# RS232.net
KiCad netlist of a schematic drawn in Altium Designer
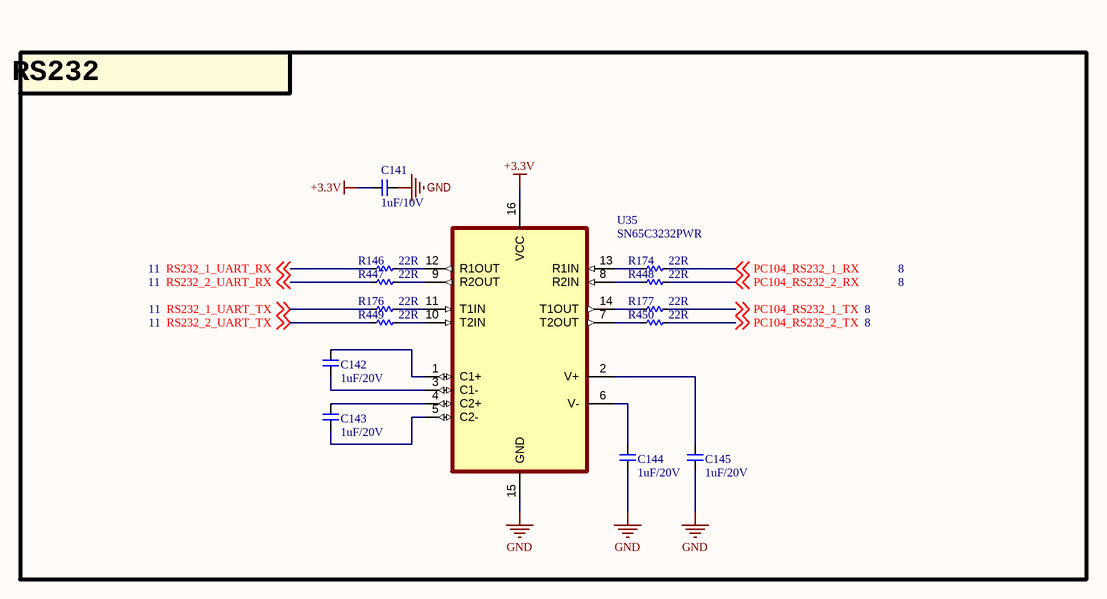
[diagram p0: RS232.SchDoc]

(export (version "E")
  (design (tool "Eeschema 10.0.6"))
  (components
    (comp (ref "C141")
      (value "1uF/10V")
      (footprint "CAP_C_1005X50_L")
      (description "CAP CHIP")
      (libsource (lib "LABLIB") (part "_CAP_C_2"))
    )
    (comp (ref "C142")
      (value "1uF/20V")
      (footprint "CAP_C_1005X50_L")
      (description "CAP CHIP")
      (libsource (lib "LABLIB") (part "_CAP_C_2"))
    )
    (comp (ref "C143")
      (value "1uF/20V")
      (footprint "CAP_C_1005X50_L")
      (description "CAP CHIP")
      (libsource (lib "LABLIB") (part "_CAP_C_2"))
    )
    (comp (ref "C144")
      (value "1uF/20V")
      (footprint "CAP_C_1005X50_L")
      (description "CAP CHIP")
      (libsource (lib "LABLIB") (part "_CAP_C_2"))
    )
    (comp (ref "C145")
      (value "1uF/20V")
      (footprint "CAP_C_1005X50_L")
      (description "CAP CHIP")
      (libsource (lib "LABLIB") (part "_CAP_C_2"))
    )
    (comp (ref "R146")
      (value "22R")
      (footprint "RES_C_1005x30_L")
      (description "RES")
      (libsource (lib "LABLIB") (part "_RES_B_2"))
    )
    (comp (ref "R174")
      (value "22R")
      (footprint "RES_C_1005x30_L")
      (description "RES")
      (libsource (lib "LABLIB") (part "_RES_B_2"))
    )
    (comp (ref "R176")
      (value "22R")
      (footprint "RES_C_1005x30_L")
      (description "RES")
      (libsource (lib "LABLIB") (part "_RES_B_2"))
    )
    (comp (ref "R177")
      (value "22R")
      (footprint "RES_C_1005x30_L")
      (description "RES")
      (libsource (lib "LABLIB") (part "_RES_B_2"))
    )
    (comp (ref "R447")
      (value "22R")
      (footprint "RES_C_1005x30_L")
      (description "RES")
      (libsource (lib "LABLIB") (part "_RES_B_2"))
    )
    (comp (ref "R448")
      (value "22R")
      (footprint "RES_C_1005x30_L")
      (description "RES")
      (libsource (lib "LABLIB") (part "_RES_B_2"))
    )
    (comp (ref "R449")
      (value "22R")
      (footprint "RES_C_1005x30_L")
      (description "RES")
      (libsource (lib "LABLIB") (part "_RES_B_2"))
    )
    (comp (ref "R450")
      (value "22R")
      (footprint "RES_C_1005x30_L")
      (description "RES")
      (libsource (lib "LABLIB") (part "_RES_B_2"))
    )
    (comp (ref "U35")
      (value "SN65C3232PWR")
      (footprint "SOP65P640X120-16N")
      (description "2/2 Transceiver Full RS232 16-TSSOP 1GHz")
      (fields (field (name "MF") "Analog Devices") (field (name "MP") "MAX3232CSE+T"))
      (libsource (lib "LABLIB") (part "IC_RS232_SN65C3232PWR"))
    )
  )
  (nets
    (net (code "1") (name "+3.3V") (class "Default")
      (node (ref "C141") (pin "2") (pinfunction "2_2") (pintype "passive"))
      (node (ref "U35") (pin "16") (pinfunction "VCC_16") (pintype "power_in"))
    )
    (net (code "2") (name "GND") (class "Default")
      (node (ref "C141") (pin "1") (pinfunction "1_1") (pintype "passive"))
      (node (ref "C144") (pin "1") (pinfunction "1_1") (pintype "passive"))
      (node (ref "C145") (pin "1") (pinfunction "1_1") (pintype "passive"))
      (node (ref "U35") (pin "15") (pinfunction "GND_15") (pintype "power_in"))
    )
    (net (code "3") (name "Net-(U35-C1+)") (class "Default")
      (node (ref "C142") (pin "1") (pinfunction "1_1") (pintype "passive"))
      (node (ref "U35") (pin "1") (pinfunction "C1+_1") (pintype "bidirectional"))
    )
    (net (code "4") (name "Net-(U35-C1-)") (class "Default")
      (node (ref "C142") (pin "2") (pinfunction "2_2") (pintype "passive"))
      (node (ref "U35") (pin "3") (pinfunction "C1-_3") (pintype "bidirectional"))
    )
    (net (code "5") (name "Net-(U35-C2+)") (class "Default")
      (node (ref "C143") (pin "1") (pinfunction "1_1") (pintype "passive"))
      (node (ref "U35") (pin "4") (pinfunction "C2+_4") (pintype "bidirectional"))
    )
    (net (code "6") (name "Net-(U35-C2-)") (class "Default")
      (node (ref "C143") (pin "2") (pinfunction "2_2") (pintype "passive"))
      (node (ref "U35") (pin "5") (pinfunction "C2-_5") (pintype "bidirectional"))
    )
    (net (code "7") (name "Net-(U35-R1IN)") (class "Default")
      (node (ref "R174") (pin "1") (pinfunction "1_1") (pintype "passive"))
      (node (ref "U35") (pin "13") (pinfunction "R1IN_13") (pintype "input"))
    )
    (net (code "8") (name "Net-(U35-R1OUT)") (class "Default")
      (node (ref "R146") (pin "2") (pinfunction "2_2") (pintype "passive"))
      (node (ref "U35") (pin "12") (pinfunction "R1OUT_12") (pintype "output"))
    )
    (net (code "9") (name "Net-(U35-R2IN)") (class "Default")
      (node (ref "R448") (pin "1") (pinfunction "1_1") (pintype "passive"))
      (node (ref "U35") (pin "8") (pinfunction "R2IN_8") (pintype "input"))
    )
    (net (code "10") (name "Net-(U35-R2OUT)") (class "Default")
      (node (ref "R447") (pin "2") (pinfunction "2_2") (pintype "passive"))
      (node (ref "U35") (pin "9") (pinfunction "R2OUT_9") (pintype "output"))
    )
    (net (code "11") (name "Net-(U35-T1IN)") (class "Default")
      (node (ref "R176") (pin "2") (pinfunction "2_2") (pintype "passive"))
      (node (ref "U35") (pin "11") (pinfunction "T1IN_11") (pintype "input"))
    )
    (net (code "12") (name "Net-(U35-T1OUT)") (class "Default")
      (node (ref "R177") (pin "1") (pinfunction "1_1") (pintype "passive"))
      (node (ref "U35") (pin "14") (pinfunction "T1OUT_14") (pintype "output"))
    )
    (net (code "13") (name "Net-(U35-T2IN)") (class "Default")
      (node (ref "R449") (pin "2") (pinfunction "2_2") (pintype "passive"))
      (node (ref "U35") (pin "10") (pinfunction "T2IN_10") (pintype "input"))
    )
    (net (code "14") (name "Net-(U35-T2OUT)") (class "Default")
      (node (ref "R450") (pin "1") (pinfunction "1_1") (pintype "passive"))
      (node (ref "U35") (pin "7") (pinfunction "T2OUT_7") (pintype "output"))
    )
    (net (code "15") (name "Net-(U35-V+)") (class "Default")
      (node (ref "C145") (pin "2") (pinfunction "2_2") (pintype "passive"))
      (node (ref "U35") (pin "2") (pinfunction "V+_2") (pintype "power_in"))
    )
    (net (code "16") (name "Net-(U35-V-)") (class "Default")
      (node (ref "C144") (pin "2") (pinfunction "2_2") (pintype "passive"))
      (node (ref "U35") (pin "6") (pinfunction "V-_6") (pintype "power_in"))
    )
    (net (code "17") (name "PC104_RS232_1_RX") (class "Default")
      (node (ref "R174") (pin "2") (pinfunction "2_2") (pintype "passive"))
    )
    (net (code "18") (name "PC104_RS232_1_TX") (class "Default")
      (node (ref "R177") (pin "2") (pinfunction "2_2") (pintype "passive"))
    )
    (net (code "19") (name "PC104_RS232_2_RX") (class "Default")
      (node (ref "R448") (pin "2") (pinfunction "2_2") (pintype "passive"))
    )
    (net (code "20") (name "PC104_RS232_2_TX") (class "Default")
      (node (ref "R450") (pin "2") (pinfunction "2_2") (pintype "passive"))
    )
    (net (code "21") (name "RS232_1_UART_RX") (class "Default")
      (node (ref "R146") (pin "1") (pinfunction "1_1") (pintype "passive"))
    )
    (net (code "22") (name "RS232_1_UART_TX") (class "Default")
      (node (ref "R176") (pin "1") (pinfunction "1_1") (pintype "passive"))
    )
    (net (code "23") (name "RS232_2_UART_RX") (class "Default")
      (node (ref "R447") (pin "1") (pinfunction "1_1") (pintype "passive"))
    )
    (net (code "24") (name "RS232_2_UART_TX") (class "Default")
      (node (ref "R449") (pin "1") (pinfunction "1_1") (pintype "passive"))
    )
  )
)
